# senseBox_I2C-Multiplexer_V11.net
KiCad netlist of a schematic drawn in EAGLE
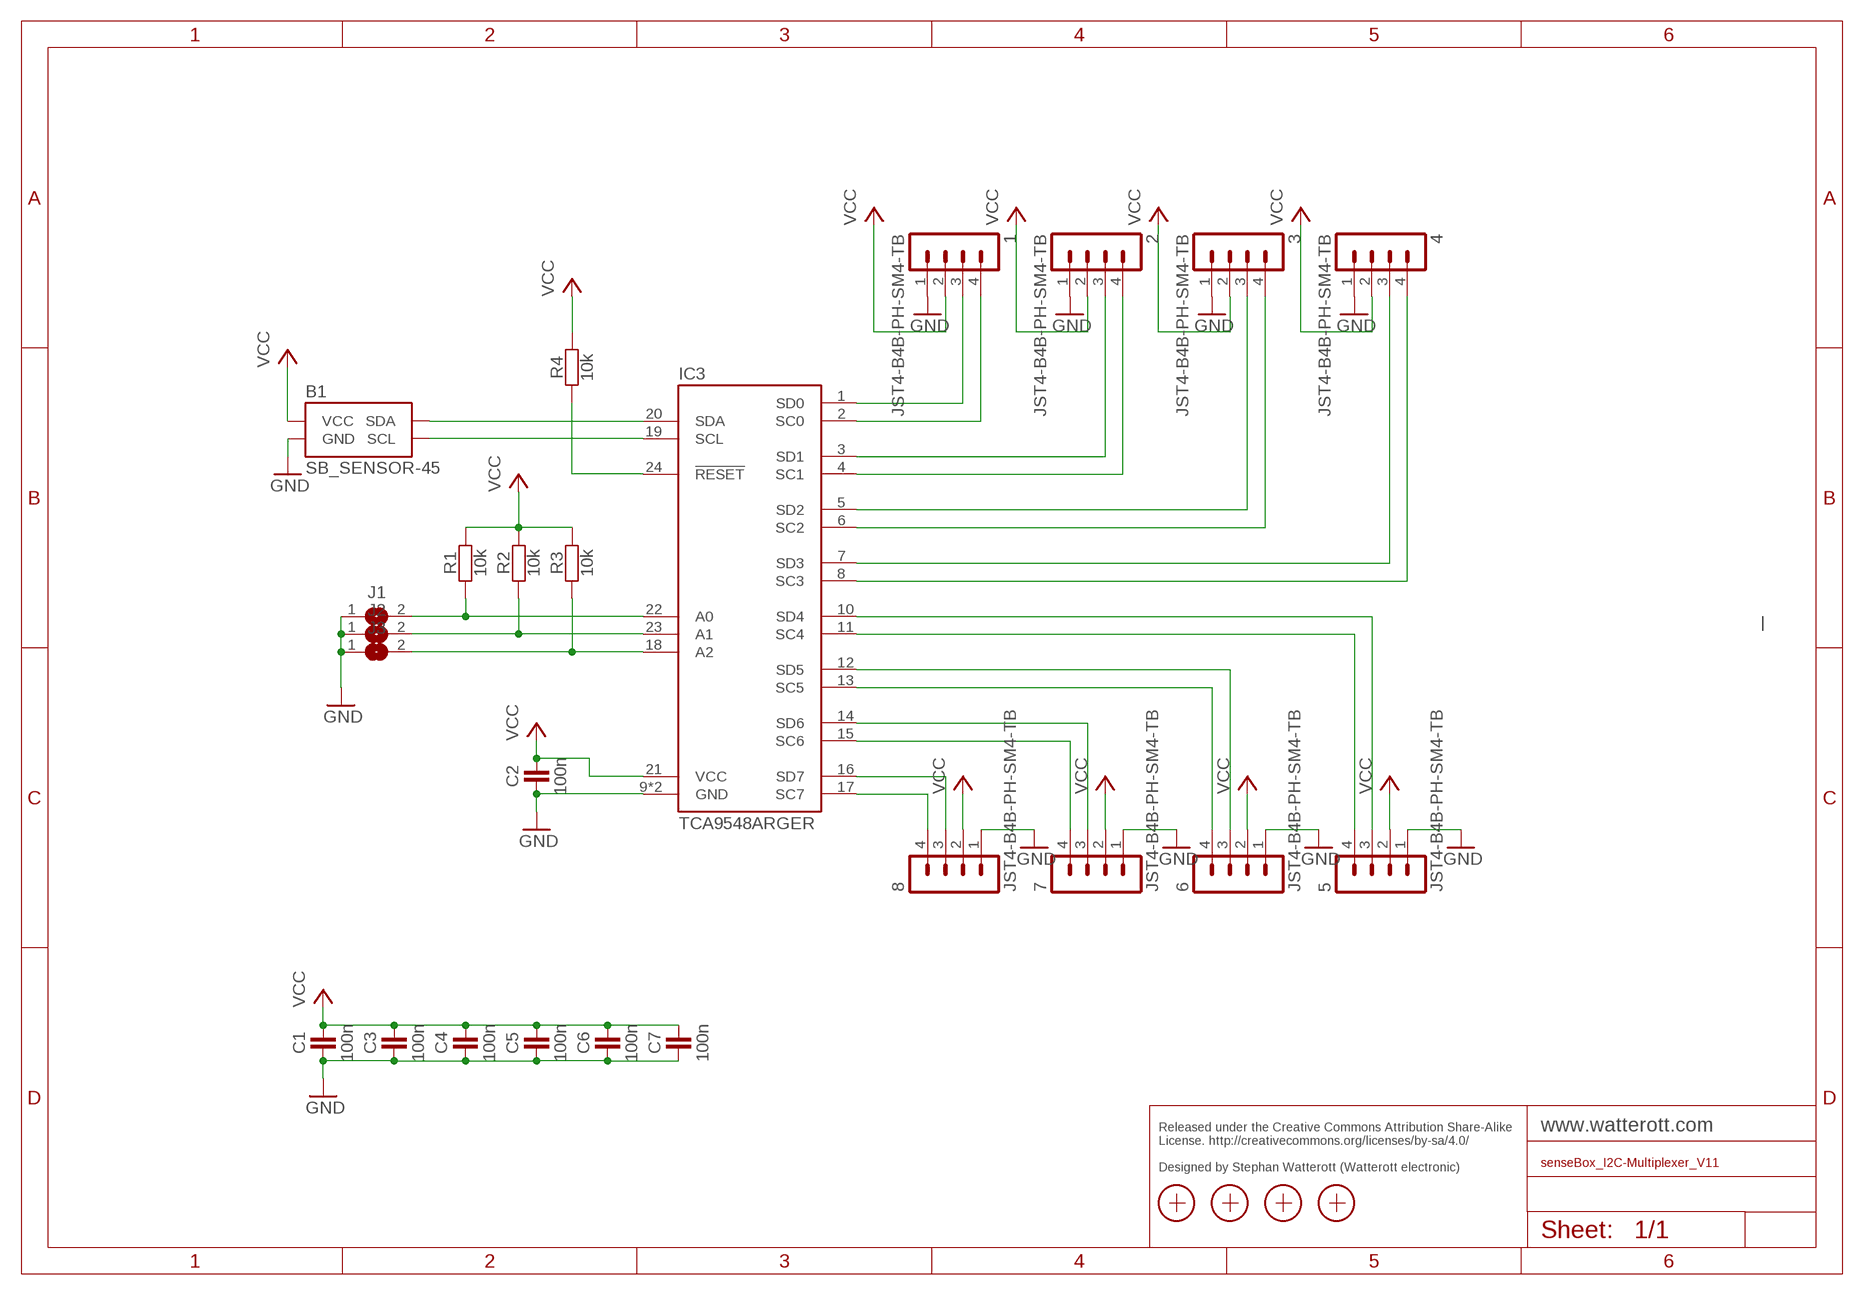
[diagram p0: schematic, sheet 1]

(export (version "E")
  (design (tool "Eeschema 10.0.6"))
  (components
    (comp (ref "1")
      (value "JST4-B4B-PH-SM4-TB")
      (footprint "eagle-import:JST_B4B-PH-SM4-TB")
      (libsource (lib "eagle-import") (part "JST4-B4B-PH-SM4-TB"))
    )
    (comp (ref "2")
      (value "JST4-B4B-PH-SM4-TB")
      (footprint "eagle-import:JST_B4B-PH-SM4-TB")
      (libsource (lib "eagle-import") (part "JST4-B4B-PH-SM4-TB"))
    )
    (comp (ref "3")
      (value "JST4-B4B-PH-SM4-TB")
      (footprint "eagle-import:JST_B4B-PH-SM4-TB")
      (libsource (lib "eagle-import") (part "JST4-B4B-PH-SM4-TB"))
    )
    (comp (ref "4")
      (value "JST4-B4B-PH-SM4-TB")
      (footprint "eagle-import:JST_B4B-PH-SM4-TB")
      (libsource (lib "eagle-import") (part "JST4-B4B-PH-SM4-TB"))
    )
    (comp (ref "5")
      (value "JST4-B4B-PH-SM4-TB")
      (footprint "eagle-import:JST_B4B-PH-SM4-TB")
      (libsource (lib "eagle-import") (part "JST4-B4B-PH-SM4-TB"))
    )
    (comp (ref "6")
      (value "JST4-B4B-PH-SM4-TB")
      (footprint "eagle-import:JST_B4B-PH-SM4-TB")
      (libsource (lib "eagle-import") (part "JST4-B4B-PH-SM4-TB"))
    )
    (comp (ref "7")
      (value "JST4-B4B-PH-SM4-TB")
      (footprint "eagle-import:JST_B4B-PH-SM4-TB")
      (libsource (lib "eagle-import") (part "JST4-B4B-PH-SM4-TB"))
    )
    (comp (ref "8")
      (value "JST4-B4B-PH-SM4-TB")
      (footprint "eagle-import:JST_B4B-PH-SM4-TB")
      (libsource (lib "eagle-import") (part "JST4-B4B-PH-SM4-TB"))
    )
    (comp (ref "B1")
      (value "SB_SENSOR-45")
      (footprint "eagle-import:SB-45X25")
      (libsource (lib "eagle-import") (part "SB_SENSOR-45"))
    )
    (comp (ref "C1")
      (value "100n")
      (footprint "eagle-import:C0402")
      (libsource (lib "eagle-import") (part "CAPACITOR-0402"))
    )
    (comp (ref "C2")
      (value "100n")
      (footprint "eagle-import:C0402")
      (libsource (lib "eagle-import") (part "CAPACITOR-0402"))
    )
    (comp (ref "C3")
      (value "100n")
      (footprint "eagle-import:C0402")
      (libsource (lib "eagle-import") (part "CAPACITOR-0402"))
    )
    (comp (ref "C4")
      (value "100n")
      (footprint "eagle-import:C0402")
      (libsource (lib "eagle-import") (part "CAPACITOR-0402"))
    )
    (comp (ref "C5")
      (value "100n")
      (footprint "eagle-import:C0402")
      (libsource (lib "eagle-import") (part "CAPACITOR-0402"))
    )
    (comp (ref "C6")
      (value "100n")
      (footprint "eagle-import:C0402")
      (libsource (lib "eagle-import") (part "CAPACITOR-0402"))
    )
    (comp (ref "C7")
      (value "100n")
      (footprint "eagle-import:C0402")
      (libsource (lib "eagle-import") (part "CAPACITOR-0402"))
    )
    (comp (ref "IC3")
      (value "TCA9548ARGER")
      (footprint "eagle-import:QFN24-PAD")
      (libsource (lib "eagle-import") (part "TCA9548ARGER"))
    )
    (comp (ref "J1")
      (value "JUMPER2-0402-NC")
      (footprint "eagle-import:JUMPER2-0402_NC")
      (libsource (lib "eagle-import") (part "JUMPER2-0402-NC"))
    )
    (comp (ref "J2")
      (value "JUMPER2-0402-NC")
      (footprint "eagle-import:JUMPER2-0402_NC")
      (libsource (lib "eagle-import") (part "JUMPER2-0402-NC"))
    )
    (comp (ref "J3")
      (value "JUMPER2-0402-NC")
      (footprint "eagle-import:JUMPER2-0402_NC")
      (libsource (lib "eagle-import") (part "JUMPER2-0402-NC"))
    )
    (comp (ref "R1")
      (value "10k")
      (footprint "eagle-import:C0402")
      (libsource (lib "eagle-import") (part "RESISTOR-0402"))
    )
    (comp (ref "R2")
      (value "10k")
      (footprint "eagle-import:C0402")
      (libsource (lib "eagle-import") (part "RESISTOR-0402"))
    )
    (comp (ref "R3")
      (value "10k")
      (footprint "eagle-import:C0402")
      (libsource (lib "eagle-import") (part "RESISTOR-0402"))
    )
    (comp (ref "R4")
      (value "10k")
      (footprint "eagle-import:C0402")
      (libsource (lib "eagle-import") (part "RESISTOR-0402"))
    )
    (comp (ref "X1")
      (value "PASSER-07")
      (footprint "eagle-import:PASSER_07MM")
      (libsource (lib "eagle-import") (part "PASSER-07"))
    )
    (comp (ref "X2")
      (value "PASSER-07")
      (footprint "eagle-import:PASSER_07MM")
      (libsource (lib "eagle-import") (part "PASSER-07"))
    )
    (comp (ref "X3")
      (value "PASSER-07")
      (footprint "eagle-import:PASSER_07MM")
      (libsource (lib "eagle-import") (part "PASSER-07"))
    )
    (comp (ref "X4")
      (value "PASSER-07")
      (footprint "eagle-import:PASSER_07MM")
      (libsource (lib "eagle-import") (part "PASSER-07"))
    )
  )
  (nets
    (net (code "1") (name "GND") (class "Default")
      (node (ref "1") (pin "1") (pinfunction "1_1") (pintype "passive"))
      (node (ref "2") (pin "1") (pinfunction "1_1") (pintype "passive"))
      (node (ref "3") (pin "1") (pinfunction "1_1") (pintype "passive"))
      (node (ref "4") (pin "1") (pinfunction "1_1") (pintype "passive"))
      (node (ref "5") (pin "1") (pinfunction "1_1") (pintype "passive"))
      (node (ref "6") (pin "1") (pinfunction "1_1") (pintype "passive"))
      (node (ref "7") (pin "1") (pinfunction "1_1") (pintype "passive"))
      (node (ref "8") (pin "1") (pinfunction "1_1") (pintype "passive"))
      (node (ref "B1") (pin "GND") (pinfunction "GND_GND") (pintype "power_in"))
      (node (ref "C1") (pin "1") (pinfunction "1_1") (pintype "passive"))
      (node (ref "C2") (pin "1") (pinfunction "1_1") (pintype "passive"))
      (node (ref "C3") (pin "1") (pinfunction "1_1") (pintype "passive"))
      (node (ref "C4") (pin "1") (pinfunction "1_1") (pintype "passive"))
      (node (ref "C5") (pin "1") (pinfunction "1_1") (pintype "passive"))
      (node (ref "C6") (pin "1") (pinfunction "1_1") (pintype "passive"))
      (node (ref "C7") (pin "1") (pinfunction "1_1") (pintype "passive"))
      (node (ref "IC3") (pin "9") (pinfunction "GND_9") (pintype "power_in"))
      (node (ref "IC3") (pin "TP") (pinfunction "GND_TP") (pintype "power_in"))
      (node (ref "J1") (pin "1") (pinfunction "1_1") (pintype "passive"))
      (node (ref "J2") (pin "1") (pinfunction "1_1") (pintype "passive"))
      (node (ref "J3") (pin "1") (pinfunction "1_1") (pintype "passive"))
    )
    (net (code "2") (name "Net-(IC3-A0)") (class "Default")
      (node (ref "IC3") (pin "22") (pinfunction "A0_22") (pintype "bidirectional"))
      (node (ref "J1") (pin "2") (pinfunction "2_2") (pintype "passive"))
      (node (ref "R1") (pin "1") (pinfunction "1_1") (pintype "passive"))
    )
    (net (code "3") (name "Net-(IC3-A1)") (class "Default")
      (node (ref "IC3") (pin "23") (pinfunction "A1_23") (pintype "bidirectional"))
      (node (ref "J2") (pin "2") (pinfunction "2_2") (pintype "passive"))
      (node (ref "R2") (pin "1") (pinfunction "1_1") (pintype "passive"))
    )
    (net (code "4") (name "Net-(IC3-A2)") (class "Default")
      (node (ref "IC3") (pin "18") (pinfunction "A2_18") (pintype "bidirectional"))
      (node (ref "J3") (pin "2") (pinfunction "2_2") (pintype "passive"))
      (node (ref "R3") (pin "1") (pinfunction "1_1") (pintype "passive"))
    )
    (net (code "5") (name "Net-(IC3-SC0)") (class "Default")
      (node (ref "1") (pin "4") (pinfunction "4_4") (pintype "passive"))
      (node (ref "IC3") (pin "2") (pinfunction "SC0_2") (pintype "bidirectional"))
    )
    (net (code "6") (name "Net-(IC3-SC1)") (class "Default")
      (node (ref "2") (pin "4") (pinfunction "4_4") (pintype "passive"))
      (node (ref "IC3") (pin "4") (pinfunction "SC1_4") (pintype "bidirectional"))
    )
    (net (code "7") (name "Net-(IC3-SC2)") (class "Default")
      (node (ref "3") (pin "4") (pinfunction "4_4") (pintype "passive"))
      (node (ref "IC3") (pin "6") (pinfunction "SC2_6") (pintype "bidirectional"))
    )
    (net (code "8") (name "Net-(IC3-SC3)") (class "Default")
      (node (ref "4") (pin "4") (pinfunction "4_4") (pintype "passive"))
      (node (ref "IC3") (pin "8") (pinfunction "SC3_8") (pintype "bidirectional"))
    )
    (net (code "9") (name "Net-(IC3-SC4)") (class "Default")
      (node (ref "5") (pin "4") (pinfunction "4_4") (pintype "passive"))
      (node (ref "IC3") (pin "11") (pinfunction "SC4_11") (pintype "bidirectional"))
    )
    (net (code "10") (name "Net-(IC3-SC5)") (class "Default")
      (node (ref "6") (pin "4") (pinfunction "4_4") (pintype "passive"))
      (node (ref "IC3") (pin "13") (pinfunction "SC5_13") (pintype "bidirectional"))
    )
    (net (code "11") (name "Net-(IC3-SC6)") (class "Default")
      (node (ref "7") (pin "4") (pinfunction "4_4") (pintype "passive"))
      (node (ref "IC3") (pin "15") (pinfunction "SC6_15") (pintype "bidirectional"))
    )
    (net (code "12") (name "Net-(IC3-SC7)") (class "Default")
      (node (ref "8") (pin "4") (pinfunction "4_4") (pintype "passive"))
      (node (ref "IC3") (pin "17") (pinfunction "SC7_17") (pintype "bidirectional"))
    )
    (net (code "13") (name "Net-(IC3-SCL)") (class "Default")
      (node (ref "B1") (pin "SCL") (pinfunction "SCL_SCL") (pintype "bidirectional"))
      (node (ref "IC3") (pin "19") (pinfunction "SCL_19") (pintype "bidirectional"))
    )
    (net (code "14") (name "Net-(IC3-SD0)") (class "Default")
      (node (ref "1") (pin "3") (pinfunction "3_3") (pintype "passive"))
      (node (ref "IC3") (pin "1") (pinfunction "SD0_1") (pintype "bidirectional"))
    )
    (net (code "15") (name "Net-(IC3-SD1)") (class "Default")
      (node (ref "2") (pin "3") (pinfunction "3_3") (pintype "passive"))
      (node (ref "IC3") (pin "3") (pinfunction "SD1_3") (pintype "bidirectional"))
    )
    (net (code "16") (name "Net-(IC3-SD2)") (class "Default")
      (node (ref "3") (pin "3") (pinfunction "3_3") (pintype "passive"))
      (node (ref "IC3") (pin "5") (pinfunction "SD2_5") (pintype "bidirectional"))
    )
    (net (code "17") (name "Net-(IC3-SD3)") (class "Default")
      (node (ref "4") (pin "3") (pinfunction "3_3") (pintype "passive"))
      (node (ref "IC3") (pin "7") (pinfunction "SD3_7") (pintype "bidirectional"))
    )
    (net (code "18") (name "Net-(IC3-SD4)") (class "Default")
      (node (ref "5") (pin "3") (pinfunction "3_3") (pintype "passive"))
      (node (ref "IC3") (pin "10") (pinfunction "SD4_10") (pintype "bidirectional"))
    )
    (net (code "19") (name "Net-(IC3-SD5)") (class "Default")
      (node (ref "6") (pin "3") (pinfunction "3_3") (pintype "passive"))
      (node (ref "IC3") (pin "12") (pinfunction "SD5_12") (pintype "bidirectional"))
    )
    (net (code "20") (name "Net-(IC3-SD6)") (class "Default")
      (node (ref "7") (pin "3") (pinfunction "3_3") (pintype "passive"))
      (node (ref "IC3") (pin "14") (pinfunction "SD6_14") (pintype "bidirectional"))
    )
    (net (code "21") (name "Net-(IC3-SD7)") (class "Default")
      (node (ref "8") (pin "3") (pinfunction "3_3") (pintype "passive"))
      (node (ref "IC3") (pin "16") (pinfunction "SD7_16") (pintype "bidirectional"))
    )
    (net (code "22") (name "Net-(IC3-SDA)") (class "Default")
      (node (ref "B1") (pin "SDA") (pinfunction "SDA_SDA") (pintype "bidirectional"))
      (node (ref "IC3") (pin "20") (pinfunction "SDA_20") (pintype "bidirectional"))
    )
    (net (code "23") (name "Net-(IC3-~{RESET})") (class "Default")
      (node (ref "IC3") (pin "24") (pinfunction "~{RESET}_24") (pintype "bidirectional"))
      (node (ref "R4") (pin "1") (pinfunction "1_1") (pintype "passive"))
    )
    (net (code "24") (name "VCC") (class "Default")
      (node (ref "1") (pin "2") (pinfunction "2_2") (pintype "passive"))
      (node (ref "2") (pin "2") (pinfunction "2_2") (pintype "passive"))
      (node (ref "3") (pin "2") (pinfunction "2_2") (pintype "passive"))
      (node (ref "4") (pin "2") (pinfunction "2_2") (pintype "passive"))
      (node (ref "5") (pin "2") (pinfunction "2_2") (pintype "passive"))
      (node (ref "6") (pin "2") (pinfunction "2_2") (pintype "passive"))
      (node (ref "7") (pin "2") (pinfunction "2_2") (pintype "passive"))
      (node (ref "8") (pin "2") (pinfunction "2_2") (pintype "passive"))
      (node (ref "B1") (pin "VCC") (pinfunction "VCC_VCC") (pintype "power_in"))
      (node (ref "C1") (pin "2") (pinfunction "2_2") (pintype "passive"))
      (node (ref "C2") (pin "2") (pinfunction "2_2") (pintype "passive"))
      (node (ref "C3") (pin "2") (pinfunction "2_2") (pintype "passive"))
      (node (ref "C4") (pin "2") (pinfunction "2_2") (pintype "passive"))
      (node (ref "C5") (pin "2") (pinfunction "2_2") (pintype "passive"))
      (node (ref "C6") (pin "2") (pinfunction "2_2") (pintype "passive"))
      (node (ref "C7") (pin "2") (pinfunction "2_2") (pintype "passive"))
      (node (ref "IC3") (pin "21") (pinfunction "VCC_21") (pintype "power_in"))
      (node (ref "R1") (pin "2") (pinfunction "2_2") (pintype "passive"))
      (node (ref "R2") (pin "2") (pinfunction "2_2") (pintype "passive"))
      (node (ref "R3") (pin "2") (pinfunction "2_2") (pintype "passive"))
      (node (ref "R4") (pin "2") (pinfunction "2_2") (pintype "passive"))
    )
  )
)
